# RTC.net
KiCad netlist of a schematic drawn in EAGLE
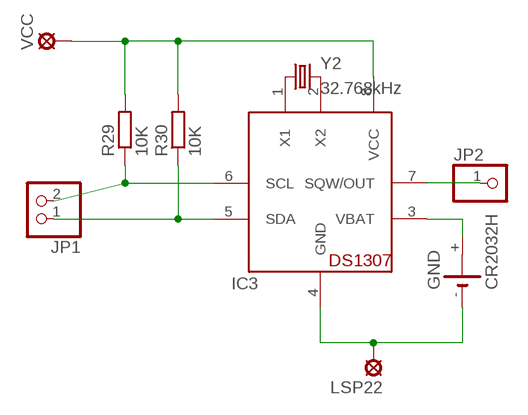
[diagram p0: schematic, sheet 1]

(export (version "E")
  (design (tool "Eeschema 10.0.6"))
  (components
    (comp (ref "GND")
      (value "CR2032H")
      (footprint "eagle-import:CR2032H")
      (libsource (lib "eagle-import") (part "CR2032H"))
    )
    (comp (ref "IC3")
      (value "DS1307")
      (footprint "eagle-import:DIL08")
      (libsource (lib "eagle-import") (part "DS1307"))
    )
    (comp (ref "JP1")
      (value "PINHD-1X2")
      (footprint "eagle-import:1X02")
      (libsource (lib "eagle-import") (part "PINHD-1X2"))
    )
    (comp (ref "JP2")
      (value "PINHD-1X1")
      (footprint "eagle-import:1X01")
      (libsource (lib "eagle-import") (part "PINHD-1X1"))
    )
    (comp (ref "LSP22")
      (value "LSP10")
      (footprint "eagle-import:LSP10")
      (libsource (lib "eagle-import") (part "LSP10"))
    )
    (comp (ref "R29")
      (value "10K")
      (footprint "eagle-import:0207_10")
      (libsource (lib "eagle-import") (part "R-EU_0207/10"))
    )
    (comp (ref "R30")
      (value "10K")
      (footprint "eagle-import:0207_10")
      (libsource (lib "eagle-import") (part "R-EU_0207/10"))
    )
    (comp (ref "VCC")
      (value "LSP10")
      (footprint "eagle-import:LSP10")
      (libsource (lib "eagle-import") (part "LSP10"))
    )
    (comp (ref "Y2")
      (value "32.768kHz")
      (footprint "eagle-import:TC26V")
      (libsource (lib "eagle-import") (part "CRYSTALTC26V"))
    )
  )
  (nets
    (net (code "1") (name "Net-(IC3-GND)") (class "Default")
      (node (ref "GND") (pin "-") (pinfunction "-_-") (pintype "passive"))
      (node (ref "IC3") (pin "4") (pinfunction "GND_4") (pintype "power_in"))
      (node (ref "LSP22") (pin "MP") (pinfunction "MP_MP") (pintype "passive"))
    )
    (net (code "2") (name "Net-(IC3-SCL)") (class "Default")
      (node (ref "IC3") (pin "6") (pinfunction "SCL_6") (pintype "bidirectional"))
      (node (ref "JP1") (pin "2") (pinfunction "2_2") (pintype "passive"))
      (node (ref "R29") (pin "1") (pinfunction "1_1") (pintype "passive"))
    )
    (net (code "3") (name "Net-(IC3-SDA)") (class "Default")
      (node (ref "IC3") (pin "5") (pinfunction "SDA_5") (pintype "bidirectional"))
      (node (ref "JP1") (pin "1") (pinfunction "1_1") (pintype "passive"))
      (node (ref "R30") (pin "1") (pinfunction "1_1") (pintype "passive"))
    )
    (net (code "4") (name "Net-(IC3-SQW{slash}OUT)") (class "Default")
      (node (ref "IC3") (pin "7") (pinfunction "SQW/OUT_7") (pintype "bidirectional"))
      (node (ref "JP2") (pin "1") (pinfunction "1_1") (pintype "passive"))
    )
    (net (code "5") (name "Net-(IC3-VBAT)") (class "Default")
      (node (ref "GND") (pin "+") (pinfunction "+_+") (pintype "passive"))
      (node (ref "IC3") (pin "3") (pinfunction "VBAT_3") (pintype "power_in"))
    )
    (net (code "6") (name "Net-(IC3-VCC)") (class "Default")
      (node (ref "IC3") (pin "8") (pinfunction "VCC_8") (pintype "power_in"))
      (node (ref "R29") (pin "2") (pinfunction "2_2") (pintype "passive"))
      (node (ref "R30") (pin "2") (pinfunction "2_2") (pintype "passive"))
      (node (ref "VCC") (pin "MP") (pinfunction "MP_MP") (pintype "passive"))
    )
    (net (code "7") (name "Net-(IC3-X1)") (class "Default")
      (node (ref "IC3") (pin "1") (pinfunction "X1_1") (pintype "passive"))
      (node (ref "Y2") (pin "1") (pinfunction "1_1") (pintype "passive"))
    )
    (net (code "8") (name "Net-(IC3-X2)") (class "Default")
      (node (ref "IC3") (pin "2") (pinfunction "X2_2") (pintype "passive"))
      (node (ref "Y2") (pin "2") (pinfunction "2_2") (pintype "passive"))
    )
    (net (code "9") (name "unconnected-(GND-+-Pad+@1)") (class "Default")
      (node (ref "GND") (pin "+@1") (pinfunction "+_+@1") (pintype "passive"))
    )
  )
)
